# PROC054D_AWR_Power_Decoupling.net
KiCad netlist of a schematic drawn in Altium Designer
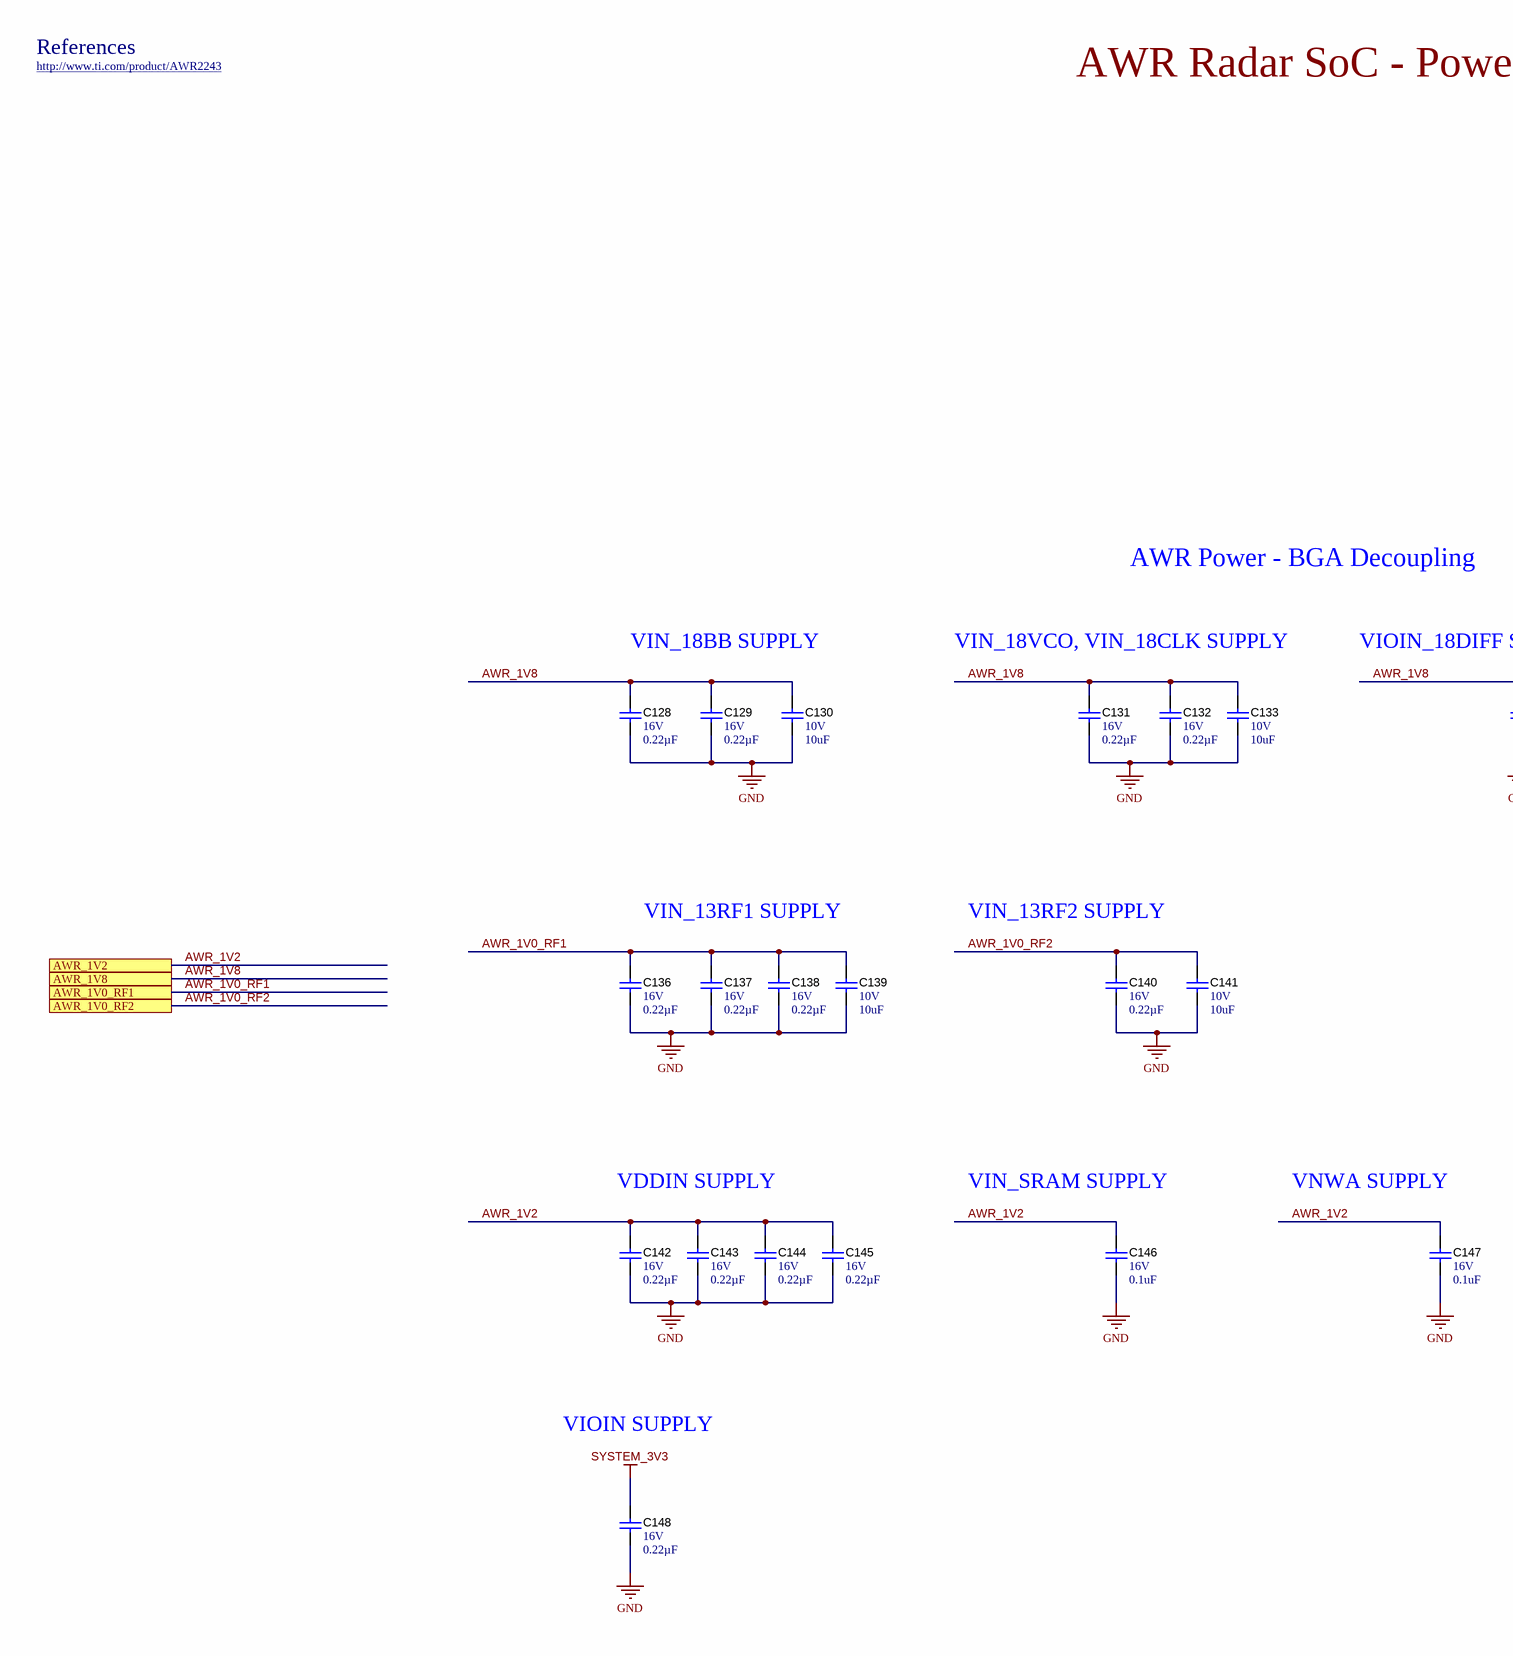
[diagram p0: PROC054D_AWR_Power_Decoupling.SchDoc, left]
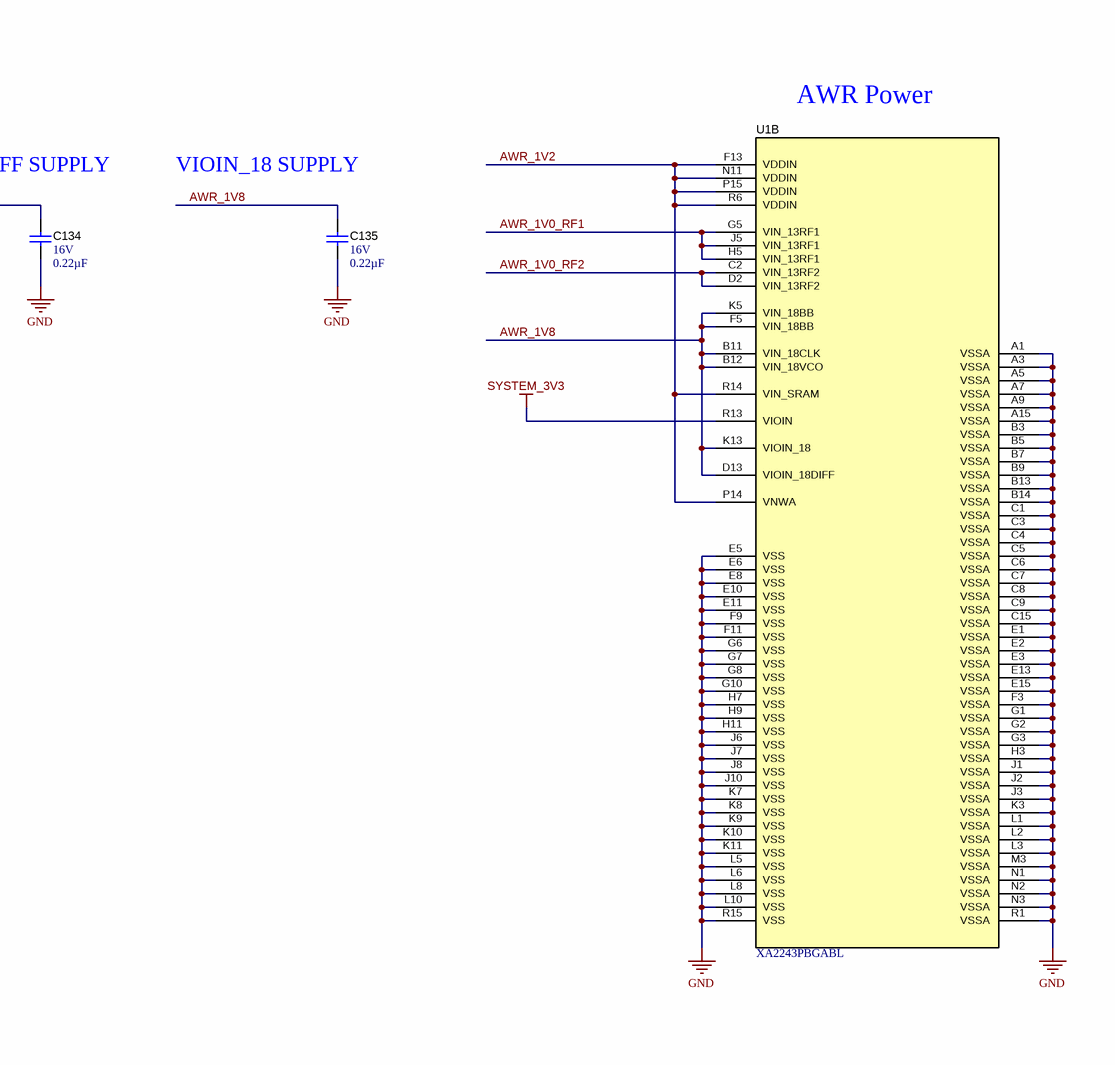
[diagram p1: PROC054D_AWR_Power_Decoupling.SchDoc, right]

(export (version "E")
  (design (tool "Eeschema 10.0.6"))
  (components
    (comp (ref "C128")
      (value "GCM155R71C224KE02D")
      (footprint "0402S")
      (description "CAP, CERM, 0.22 µF, 16 V,+/- 10%, X7R, AEC-Q200 Grade 1, 0402")
      (fields
        (field (name "MANUFACTURER") "MuRata")
        (field (name "VDC_V") "16V")
        (field (name "VALUEDISPLAYED") "0.22µF")
      )
      (libsource (lib "Altium Vault - TI") (part "CMP-0078265-1"))
    )
    (comp (ref "C129")
      (value "GCM155R71C224KE02D")
      (footprint "0402S")
      (description "CAP, CERM, 0.22 µF, 16 V,+/- 10%, X7R, AEC-Q200 Grade 1, 0402")
      (fields
        (field (name "MANUFACTURER") "MuRata")
        (field (name "VDC_V") "16V")
        (field (name "VALUEDISPLAYED") "0.22µF")
      )
      (libsource (lib "Altium Vault - TI") (part "CMP-0078265-1"))
    )
    (comp (ref "C130")
      (value "GCM21BR71A106KE22L")
      (footprint "0805L")
      (description "CAP, CERM, 10 uF, 10 V, +/- 10%, X7R, 0805")
      (fields
        (field (name "MANUFACTURER") "MuRata")
        (field (name "VDC_V") "10V")
        (field (name "VALUEDISPLAYED") "10uF")
        (field (name "PUBLISHER") "Texas Instruments")
      )
      (libsource (lib "Altium Vault - TI") (part "CMP-0008017-2"))
    )
    (comp (ref "C131")
      (value "GCM155R71C224KE02D")
      (footprint "0402S")
      (description "CAP, CERM, 0.22 µF, 16 V,+/- 10%, X7R, AEC-Q200 Grade 1, 0402")
      (fields
        (field (name "MANUFACTURER") "MuRata")
        (field (name "VDC_V") "16V")
        (field (name "VALUEDISPLAYED") "0.22µF")
      )
      (libsource (lib "Altium Vault - TI") (part "CMP-0078265-1"))
    )
    (comp (ref "C132")
      (value "GCM155R71C224KE02D")
      (footprint "0402S")
      (description "CAP, CERM, 0.22 µF, 16 V,+/- 10%, X7R, AEC-Q200 Grade 1, 0402")
      (fields
        (field (name "MANUFACTURER") "MuRata")
        (field (name "VDC_V") "16V")
        (field (name "VALUEDISPLAYED") "0.22µF")
      )
      (libsource (lib "Altium Vault - TI") (part "CMP-0078265-1"))
    )
    (comp (ref "C133")
      (value "GCM21BR71A106KE22L")
      (footprint "0805L")
      (description "CAP, CERM, 10 uF, 10 V, +/- 10%, X7R, 0805")
      (fields
        (field (name "MANUFACTURER") "MuRata")
        (field (name "VDC_V") "10V")
        (field (name "VALUEDISPLAYED") "10uF")
        (field (name "PUBLISHER") "Texas Instruments")
      )
      (libsource (lib "Altium Vault - TI") (part "CMP-0008017-2"))
    )
    (comp (ref "C134")
      (value "GCM155R71C224KE02D")
      (footprint "0402S")
      (description "CAP, CERM, 0.22 µF, 16 V,+/- 10%, X7R, AEC-Q200 Grade 1, 0402")
      (fields
        (field (name "MANUFACTURER") "MuRata")
        (field (name "VDC_V") "16V")
        (field (name "VALUEDISPLAYED") "0.22µF")
      )
      (libsource (lib "Altium Vault - TI") (part "CMP-0078265-1"))
    )
    (comp (ref "C135")
      (value "GCM155R71C224KE02D")
      (footprint "0402S")
      (description "CAP, CERM, 0.22 µF, 16 V,+/- 10%, X7R, AEC-Q200 Grade 1, 0402")
      (fields
        (field (name "MANUFACTURER") "MuRata")
        (field (name "VDC_V") "16V")
        (field (name "VALUEDISPLAYED") "0.22µF")
      )
      (libsource (lib "Altium Vault - TI") (part "CMP-0078265-1"))
    )
    (comp (ref "C136")
      (value "GCM155R71C224KE02D")
      (footprint "0402S")
      (description "CAP, CERM, 0.22 µF, 16 V,+/- 10%, X7R, AEC-Q200 Grade 1, 0402")
      (fields
        (field (name "MANUFACTURER") "MuRata")
        (field (name "VDC_V") "16V")
        (field (name "VALUEDISPLAYED") "0.22µF")
      )
      (libsource (lib "Altium Vault - TI") (part "CMP-0078265-1"))
    )
    (comp (ref "C137")
      (value "GCM155R71C224KE02D")
      (footprint "0402S")
      (description "CAP, CERM, 0.22 µF, 16 V,+/- 10%, X7R, AEC-Q200 Grade 1, 0402")
      (fields
        (field (name "MANUFACTURER") "MuRata")
        (field (name "VDC_V") "16V")
        (field (name "VALUEDISPLAYED") "0.22µF")
      )
      (libsource (lib "Altium Vault - TI") (part "CMP-0078265-1"))
    )
    (comp (ref "C138")
      (value "GCM155R71C224KE02D")
      (footprint "0402S")
      (description "CAP, CERM, 0.22 µF, 16 V,+/- 10%, X7R, AEC-Q200 Grade 1, 0402")
      (fields
        (field (name "MANUFACTURER") "MuRata")
        (field (name "VDC_V") "16V")
        (field (name "VALUEDISPLAYED") "0.22µF")
      )
      (libsource (lib "Altium Vault - TI") (part "CMP-0078265-1"))
    )
    (comp (ref "C139")
      (value "GCM21BR71A106KE22L")
      (footprint "0805L")
      (description "CAP, CERM, 10 uF, 10 V, +/- 10%, X7R, 0805")
      (fields
        (field (name "MANUFACTURER") "MuRata")
        (field (name "VDC_V") "10V")
        (field (name "VALUEDISPLAYED") "10uF")
        (field (name "PUBLISHER") "Texas Instruments")
      )
      (libsource (lib "Altium Vault - TI") (part "CMP-0008017-2"))
    )
    (comp (ref "C140")
      (value "GCM155R71C224KE02D")
      (footprint "0402S")
      (description "CAP, CERM, 0.22 µF, 16 V,+/- 10%, X7R, AEC-Q200 Grade 1, 0402")
      (fields
        (field (name "MANUFACTURER") "MuRata")
        (field (name "VDC_V") "16V")
        (field (name "VALUEDISPLAYED") "0.22µF")
      )
      (libsource (lib "Altium Vault - TI") (part "CMP-0078265-1"))
    )
    (comp (ref "C141")
      (value "GCM21BR71A106KE22L")
      (footprint "0805L")
      (description "CAP, CERM, 10 uF, 10 V, +/- 10%, X7R, 0805")
      (fields
        (field (name "MANUFACTURER") "MuRata")
        (field (name "VDC_V") "10V")
        (field (name "VALUEDISPLAYED") "10uF")
        (field (name "PUBLISHER") "Texas Instruments")
      )
      (libsource (lib "Altium Vault - TI") (part "CMP-0008017-2"))
    )
    (comp (ref "C142")
      (value "GCM155R71C224KE02D")
      (footprint "0402S")
      (description "CAP, CERM, 0.22 µF, 16 V,+/- 10%, X7R, AEC-Q200 Grade 1, 0402")
      (fields
        (field (name "MANUFACTURER") "MuRata")
        (field (name "VDC_V") "16V")
        (field (name "VALUEDISPLAYED") "0.22µF")
      )
      (libsource (lib "Altium Vault - TI") (part "CMP-0078265-1"))
    )
    (comp (ref "C143")
      (value "GCM155R71C224KE02D")
      (footprint "0402S")
      (description "CAP, CERM, 0.22 µF, 16 V,+/- 10%, X7R, AEC-Q200 Grade 1, 0402")
      (fields
        (field (name "MANUFACTURER") "MuRata")
        (field (name "VDC_V") "16V")
        (field (name "VALUEDISPLAYED") "0.22µF")
      )
      (libsource (lib "Altium Vault - TI") (part "CMP-0078265-1"))
    )
    (comp (ref "C144")
      (value "GCM155R71C224KE02D")
      (footprint "0402S")
      (description "CAP, CERM, 0.22 µF, 16 V,+/- 10%, X7R, AEC-Q200 Grade 1, 0402")
      (fields
        (field (name "MANUFACTURER") "MuRata")
        (field (name "VDC_V") "16V")
        (field (name "VALUEDISPLAYED") "0.22µF")
      )
      (libsource (lib "Altium Vault - TI") (part "CMP-0078265-1"))
    )
    (comp (ref "C145")
      (value "GCM155R71C224KE02D")
      (footprint "0402S")
      (description "CAP, CERM, 0.22 µF, 16 V,+/- 10%, X7R, AEC-Q200 Grade 1, 0402")
      (fields
        (field (name "MANUFACTURER") "MuRata")
        (field (name "VDC_V") "16V")
        (field (name "VALUEDISPLAYED") "0.22µF")
      )
      (libsource (lib "Altium Vault - TI") (part "CMP-0078265-1"))
    )
    (comp (ref "C146")
      (value "GCM155R71C104KA55D")
      (footprint "0402S")
      (description "CAP, CERM, 0.1 uF, 16 V, +/- 10%, X7R, 0402")
      (fields
        (field (name "MANUFACTURER") "MuRata")
        (field (name "VDC_V") "16V")
        (field (name "VALUEDISPLAYED") "0.1uF")
        (field (name "PUBLISHER") "Texas Instruments")
      )
      (libsource (lib "Altium Vault - TI") (part "Capacitor"))
    )
    (comp (ref "C147")
      (value "GCM155R71C104KA55D")
      (footprint "0402S")
      (description "CAP, CERM, 0.1 uF, 16 V, +/- 10%, X7R, 0402")
      (fields
        (field (name "MANUFACTURER") "MuRata")
        (field (name "VDC_V") "16V")
        (field (name "VALUEDISPLAYED") "0.1uF")
        (field (name "PUBLISHER") "Texas Instruments")
      )
      (libsource (lib "Altium Vault - TI") (part "Capacitor"))
    )
    (comp (ref "C148")
      (value "GCM155R71C224KE02D")
      (footprint "0402S")
      (description "CAP, CERM, 0.22 µF, 16 V,+/- 10%, X7R, AEC-Q200 Grade 1, 0402")
      (fields
        (field (name "MANUFACTURER") "MuRata")
        (field (name "VDC_V") "16V")
        (field (name "VALUEDISPLAYED") "0.22µF")
      )
      (libsource (lib "Altium Vault - TI") (part "CMP-0078265-1"))
    )
    (comp (ref "U1")
      (value "XA2243PBGABL")
      (footprint "ABL0161A")
      (description "Single Chip 77 and 79 GHz FMCW Transceiver, ABL0161A (FCBGA-161)")
      (fields (field (name "MANUFACTURER") "Texas Instruments") (field (name "PARTNUMBER") "XA2243PBGABL"))
      (libsource (lib "Altium Vault - TI") (part "AR1243"))
    )
  )
  (nets
    (net (code "1") (name "/AWR_1V0_RF1") (class "Default")
      (node (ref "C136") (pin "1") (pinfunction "1_1") (pintype "passive"))
      (node (ref "C137") (pin "1") (pinfunction "1_1") (pintype "passive"))
      (node (ref "C138") (pin "1") (pinfunction "1_1") (pintype "passive"))
      (node (ref "C139") (pin "1") (pinfunction "1_1") (pintype "passive"))
      (node (ref "U1") (pin "G5") (pinfunction "VIN_13RF1_G5") (pintype "power_in"))
      (node (ref "U1") (pin "H5") (pinfunction "VIN_13RF1_H5") (pintype "power_in"))
      (node (ref "U1") (pin "J5") (pinfunction "VIN_13RF1_J5") (pintype "power_in"))
    )
    (net (code "2") (name "/AWR_1V0_RF2") (class "Default")
      (node (ref "C140") (pin "1") (pinfunction "1_1") (pintype "passive"))
      (node (ref "C141") (pin "1") (pinfunction "1_1") (pintype "passive"))
      (node (ref "U1") (pin "C2") (pinfunction "VIN_13RF2_C2") (pintype "power_in"))
      (node (ref "U1") (pin "D2") (pinfunction "VIN_13RF2_D2") (pintype "power_in"))
    )
    (net (code "3") (name "/AWR_1V2") (class "Default")
      (node (ref "C142") (pin "1") (pinfunction "1_1") (pintype "passive"))
      (node (ref "C143") (pin "1") (pinfunction "1_1") (pintype "passive"))
      (node (ref "C144") (pin "1") (pinfunction "1_1") (pintype "passive"))
      (node (ref "C145") (pin "1") (pinfunction "1_1") (pintype "passive"))
      (node (ref "C146") (pin "1") (pinfunction "1_1") (pintype "passive"))
      (node (ref "C147") (pin "1") (pinfunction "1_1") (pintype "passive"))
      (node (ref "U1") (pin "F13") (pinfunction "VDDIN_F13") (pintype "power_in"))
      (node (ref "U1") (pin "N11") (pinfunction "VDDIN_N11") (pintype "power_in"))
      (node (ref "U1") (pin "P14") (pinfunction "VNWA_P14") (pintype "power_in"))
      (node (ref "U1") (pin "P15") (pinfunction "VDDIN_P15") (pintype "power_in"))
      (node (ref "U1") (pin "R14") (pinfunction "VIN_SRAM_R14") (pintype "power_in"))
      (node (ref "U1") (pin "R6") (pinfunction "VDDIN_R6") (pintype "power_in"))
    )
    (net (code "4") (name "/AWR_1V8") (class "Default")
      (node (ref "C128") (pin "1") (pinfunction "1_1") (pintype "passive"))
      (node (ref "C129") (pin "1") (pinfunction "1_1") (pintype "passive"))
      (node (ref "C130") (pin "1") (pinfunction "1_1") (pintype "passive"))
      (node (ref "C131") (pin "1") (pinfunction "1_1") (pintype "passive"))
      (node (ref "C132") (pin "1") (pinfunction "1_1") (pintype "passive"))
      (node (ref "C133") (pin "1") (pinfunction "1_1") (pintype "passive"))
      (node (ref "C134") (pin "1") (pinfunction "1_1") (pintype "passive"))
      (node (ref "C135") (pin "1") (pinfunction "1_1") (pintype "passive"))
      (node (ref "U1") (pin "B11") (pinfunction "VIN_18CLK_B11") (pintype "power_in"))
      (node (ref "U1") (pin "B12") (pinfunction "VIN_18VCO_B12") (pintype "power_in"))
      (node (ref "U1") (pin "D13") (pinfunction "VIOIN_18DIFF_D13") (pintype "power_in"))
      (node (ref "U1") (pin "F5") (pinfunction "VIN_18BB_F5") (pintype "power_in"))
      (node (ref "U1") (pin "K13") (pinfunction "VIOIN_18_K13") (pintype "power_in"))
      (node (ref "U1") (pin "K5") (pinfunction "VIN_18BB_K5") (pintype "power_in"))
    )
    (net (code "5") (name "GND") (class "Default")
      (node (ref "C128") (pin "2") (pinfunction "2_2") (pintype "passive"))
      (node (ref "C129") (pin "2") (pinfunction "2_2") (pintype "passive"))
      (node (ref "C130") (pin "2") (pinfunction "2_2") (pintype "passive"))
      (node (ref "C131") (pin "2") (pinfunction "2_2") (pintype "passive"))
      (node (ref "C132") (pin "2") (pinfunction "2_2") (pintype "passive"))
      (node (ref "C133") (pin "2") (pinfunction "2_2") (pintype "passive"))
      (node (ref "C134") (pin "2") (pinfunction "2_2") (pintype "passive"))
      (node (ref "C135") (pin "2") (pinfunction "2_2") (pintype "passive"))
      (node (ref "C136") (pin "2") (pinfunction "2_2") (pintype "passive"))
      (node (ref "C137") (pin "2") (pinfunction "2_2") (pintype "passive"))
      (node (ref "C138") (pin "2") (pinfunction "2_2") (pintype "passive"))
      (node (ref "C139") (pin "2") (pinfunction "2_2") (pintype "passive"))
      (node (ref "C140") (pin "2") (pinfunction "2_2") (pintype "passive"))
      (node (ref "C141") (pin "2") (pinfunction "2_2") (pintype "passive"))
      (node (ref "C142") (pin "2") (pinfunction "2_2") (pintype "passive"))
      (node (ref "C143") (pin "2") (pinfunction "2_2") (pintype "passive"))
      (node (ref "C144") (pin "2") (pinfunction "2_2") (pintype "passive"))
      (node (ref "C145") (pin "2") (pinfunction "2_2") (pintype "passive"))
      (node (ref "C146") (pin "2") (pinfunction "2_2") (pintype "passive"))
      (node (ref "C147") (pin "2") (pinfunction "2_2") (pintype "passive"))
      (node (ref "C148") (pin "2") (pinfunction "2_2") (pintype "passive"))
      (node (ref "U1") (pin "A1") (pinfunction "VSSA_A1") (pintype "power_in"))
      (node (ref "U1") (pin "A15") (pinfunction "VSSA_A15") (pintype "power_in"))
      (node (ref "U1") (pin "A3") (pinfunction "VSSA_A3") (pintype "power_in"))
      (node (ref "U1") (pin "A5") (pinfunction "VSSA_A5") (pintype "power_in"))
      (node (ref "U1") (pin "A7") (pinfunction "VSSA_A7") (pintype "power_in"))
      (node (ref "U1") (pin "A9") (pinfunction "VSSA_A9") (pintype "power_in"))
      (node (ref "U1") (pin "B13") (pinfunction "VSSA_B13") (pintype "power_in"))
      (node (ref "U1") (pin "B14") (pinfunction "VSSA_B14") (pintype "power_in"))
      (node (ref "U1") (pin "B3") (pinfunction "VSSA_B3") (pintype "power_in"))
      (node (ref "U1") (pin "B5") (pinfunction "VSSA_B5") (pintype "power_in"))
      (node (ref "U1") (pin "B7") (pinfunction "VSSA_B7") (pintype "power_in"))
      (node (ref "U1") (pin "B9") (pinfunction "VSSA_B9") (pintype "power_in"))
      (node (ref "U1") (pin "C1") (pinfunction "VSSA_C1") (pintype "power_in"))
      (node (ref "U1") (pin "C15") (pinfunction "VSSA_C15") (pintype "power_in"))
      (node (ref "U1") (pin "C3") (pinfunction "VSSA_C3") (pintype "power_in"))
      (node (ref "U1") (pin "C4") (pinfunction "VSSA_C4") (pintype "power_in"))
      (node (ref "U1") (pin "C5") (pinfunction "VSSA_C5") (pintype "power_in"))
      (node (ref "U1") (pin "C6") (pinfunction "VSSA_C6") (pintype "power_in"))
      (node (ref "U1") (pin "C7") (pinfunction "VSSA_C7") (pintype "power_in"))
      (node (ref "U1") (pin "C8") (pinfunction "VSSA_C8") (pintype "power_in"))
      (node (ref "U1") (pin "C9") (pinfunction "VSSA_C9") (pintype "power_in"))
      (node (ref "U1") (pin "E1") (pinfunction "VSSA_E1") (pintype "power_in"))
      (node (ref "U1") (pin "E10") (pinfunction "VSS_E10") (pintype "power_in"))
      (node (ref "U1") (pin "E11") (pinfunction "VSS_E11") (pintype "power_in"))
      (node (ref "U1") (pin "E13") (pinfunction "VSSA_E13") (pintype "power_in"))
      (node (ref "U1") (pin "E15") (pinfunction "VSSA_E15") (pintype "power_in"))
      (node (ref "U1") (pin "E2") (pinfunction "VSSA_E2") (pintype "power_in"))
      (node (ref "U1") (pin "E3") (pinfunction "VSSA_E3") (pintype "power_in"))
      (node (ref "U1") (pin "E5") (pinfunction "VSS_E5") (pintype "power_in"))
      (node (ref "U1") (pin "E6") (pinfunction "VSS_E6") (pintype "power_in"))
      (node (ref "U1") (pin "E8") (pinfunction "VSS_E8") (pintype "power_in"))
      (node (ref "U1") (pin "F11") (pinfunction "VSS_F11") (pintype "power_in"))
      (node (ref "U1") (pin "F3") (pinfunction "VSSA_F3") (pintype "power_in"))
      (node (ref "U1") (pin "F9") (pinfunction "VSS_F9") (pintype "power_in"))
      (node (ref "U1") (pin "G1") (pinfunction "VSSA_G1") (pintype "power_in"))
      (node (ref "U1") (pin "G10") (pinfunction "VSS_G10") (pintype "power_in"))
      (node (ref "U1") (pin "G2") (pinfunction "VSSA_G2") (pintype "power_in"))
      (node (ref "U1") (pin "G3") (pinfunction "VSSA_G3") (pintype "power_in"))
      (node (ref "U1") (pin "G6") (pinfunction "VSS_G6") (pintype "power_in"))
      (node (ref "U1") (pin "G7") (pinfunction "VSS_G7") (pintype "power_in"))
      (node (ref "U1") (pin "G8") (pinfunction "VSS_G8") (pintype "power_in"))
      (node (ref "U1") (pin "H11") (pinfunction "VSS_H11") (pintype "power_in"))
      (node (ref "U1") (pin "H3") (pinfunction "VSSA_H3") (pintype "power_in"))
      (node (ref "U1") (pin "H7") (pinfunction "VSS_H7") (pintype "power_in"))
      (node (ref "U1") (pin "H9") (pinfunction "VSS_H9") (pintype "power_in"))
      (node (ref "U1") (pin "J1") (pinfunction "VSSA_J1") (pintype "power_in"))
      (node (ref "U1") (pin "J10") (pinfunction "VSS_J10") (pintype "power_in"))
      (node (ref "U1") (pin "J2") (pinfunction "VSSA_J2") (pintype "power_in"))
      (node (ref "U1") (pin "J3") (pinfunction "VSSA_J3") (pintype "power_in"))
      (node (ref "U1") (pin "J6") (pinfunction "VSS_J6") (pintype "power_in"))
      (node (ref "U1") (pin "J7") (pinfunction "VSS_J7") (pintype "power_in"))
      (node (ref "U1") (pin "J8") (pinfunction "VSS_J8") (pintype "power_in"))
      (node (ref "U1") (pin "K10") (pinfunction "VSS_K10") (pintype "power_in"))
      (node (ref "U1") (pin "K11") (pinfunction "VSS_K11") (pintype "power_in"))
      (node (ref "U1") (pin "K3") (pinfunction "VSSA_K3") (pintype "power_in"))
      (node (ref "U1") (pin "K7") (pinfunction "VSS_K7") (pintype "power_in"))
      (node (ref "U1") (pin "K8") (pinfunction "VSS_K8") (pintype "power_in"))
      (node (ref "U1") (pin "K9") (pinfunction "VSS_K9") (pintype "power_in"))
      (node (ref "U1") (pin "L1") (pinfunction "VSSA_L1") (pintype "power_in"))
      (node (ref "U1") (pin "L10") (pinfunction "VSS_L10") (pintype "power_in"))
      (node (ref "U1") (pin "L2") (pinfunction "VSSA_L2") (pintype "power_in"))
      (node (ref "U1") (pin "L3") (pinfunction "VSSA_L3") (pintype "power_in"))
      (node (ref "U1") (pin "L5") (pinfunction "VSS_L5") (pintype "power_in"))
      (node (ref "U1") (pin "L6") (pinfunction "VSS_L6") (pintype "power_in"))
      (node (ref "U1") (pin "L8") (pinfunction "VSS_L8") (pintype "power_in"))
      (node (ref "U1") (pin "M3") (pinfunction "VSSA_M3") (pintype "power_in"))
      (node (ref "U1") (pin "N1") (pinfunction "VSSA_N1") (pintype "power_in"))
      (node (ref "U1") (pin "N2") (pinfunction "VSSA_N2") (pintype "power_in"))
      (node (ref "U1") (pin "N3") (pinfunction "VSSA_N3") (pintype "power_in"))
      (node (ref "U1") (pin "R1") (pinfunction "VSSA_R1") (pintype "power_in"))
      (node (ref "U1") (pin "R15") (pinfunction "VSS_R15") (pintype "power_in"))
    )
    (net (code "6") (name "SYSTEM_3V3") (class "Default")
      (node (ref "C148") (pin "1") (pinfunction "1_1") (pintype "passive"))
      (node (ref "U1") (pin "R13") (pinfunction "VIOIN_R13") (pintype "power_in"))
    )
  )
)
